# branch.net
KiCad netlist of a schematic drawn in EAGLE
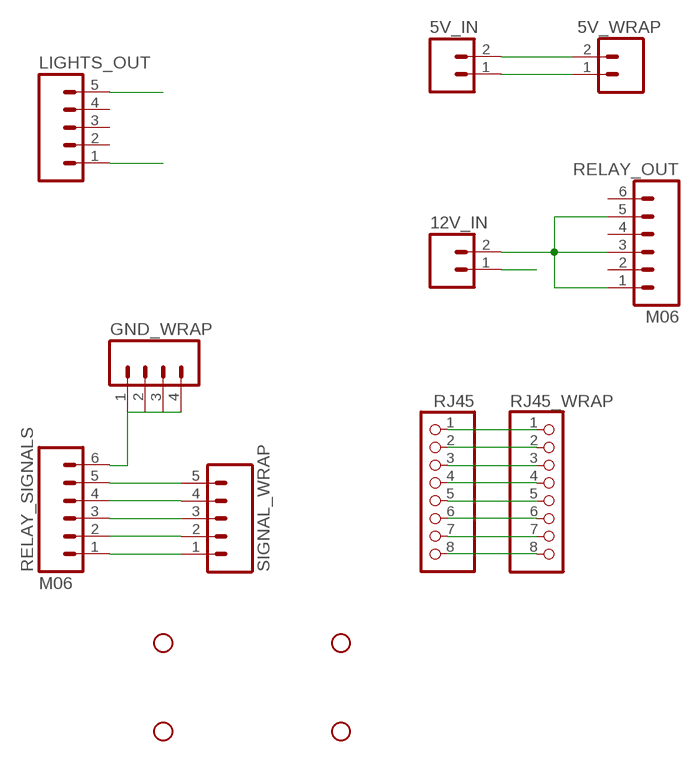
[diagram p0: schematic, sheet 1]

(export (version "E")
  (design (tool "Eeschema 10.0.6"))
  (components
    (comp (ref "5V_IN")
      (value "M021X02-MTA")
      (footprint "eagle-import:1X02-MTA")
      (fields (field (name "PARTNUMBER") "A1921-ND"))
      (libsource (lib "eagle-import") (part "M021X02-MTA"))
    )
    (comp (ref "5V_WRAP")
      (value "M02PTH")
      (footprint "eagle-import:1X02")
      (libsource (lib "eagle-import") (part "M02PTH"))
    )
    (comp (ref "12V_IN")
      (value "M021X02-MTA")
      (footprint "eagle-import:1X02-MTA")
      (fields (field (name "PARTNUMBER") "A1921-ND"))
      (libsource (lib "eagle-import") (part "M021X02-MTA"))
    )
    (comp (ref "GND_WRAP")
      (value "M04PTH")
      (footprint "eagle-import:1X04")
      (libsource (lib "eagle-import") (part "M04PTH"))
    )
    (comp (ref "LIGHTS_OUT")
      (value "M05MTA")
      (footprint "eagle-import:1X05-MTA")
      (fields (field (name "PARTNUMBER") "A19471-ND"))
      (libsource (lib "eagle-import") (part "M05MTA"))
    )
    (comp (ref "RELAY_OUT")
      (value "M06")
      (footprint "eagle-import:1X06-MTA")
      (fields (field (name "PARTNUMBER") "A1923-ND"))
      (libsource (lib "eagle-import") (part "M06"))
    )
    (comp (ref "RELAY_SIGNALS")
      (value "M06")
      (footprint "eagle-import:1X06-MTA")
      (fields (field (name "PARTNUMBER") "A1923-ND"))
      (libsource (lib "eagle-import") (part "M06"))
    )
    (comp (ref "RJ45")
      (value "PINHD-1X8")
      (footprint "eagle-import:1X08")
      (fields (field (name "PARTNUMBER") "965"))
      (libsource (lib "eagle-import") (part "PINHD-1X8"))
    )
    (comp (ref "RJ45_WRAP")
      (value "PINHD-1X8")
      (footprint "eagle-import:1X08")
      (fields (field (name "PARTNUMBER") "965"))
      (libsource (lib "eagle-import") (part "PINHD-1X8"))
    )
    (comp (ref "SIGNAL_WRAP")
      (value "M05PTH")
      (footprint "eagle-import:1X05")
      (fields (field (name "PARTNUMBER") "965"))
      (libsource (lib "eagle-import") (part "M05PTH"))
    )
    (comp (ref "STANDOFF1")
      (value "STAND-OFF")
      (footprint "eagle-import:STAND-OFF")
      (libsource (lib "eagle-import") (part "STAND-OFF"))
    )
    (comp (ref "STANDOFF2")
      (value "STAND-OFF")
      (footprint "eagle-import:STAND-OFF")
      (libsource (lib "eagle-import") (part "STAND-OFF"))
    )
    (comp (ref "STANDOFF3")
      (value "STAND-OFF")
      (footprint "eagle-import:STAND-OFF")
      (libsource (lib "eagle-import") (part "STAND-OFF"))
    )
    (comp (ref "STANDOFF4")
      (value "STAND-OFF")
      (footprint "eagle-import:STAND-OFF")
      (libsource (lib "eagle-import") (part "STAND-OFF"))
    )
  )
  (nets
    (net (code "1") (name "/GND") (class "Default")
      (node (ref "12V_IN") (pin "1") (pinfunction "1_1") (pintype "passive"))
      (node (ref "5V_IN") (pin "1") (pinfunction "1_1") (pintype "passive"))
      (node (ref "5V_WRAP") (pin "1") (pinfunction "1_1") (pintype "passive"))
      (node (ref "GND_WRAP") (pin "1") (pinfunction "1_1") (pintype "passive"))
      (node (ref "GND_WRAP") (pin "2") (pinfunction "2_2") (pintype "passive"))
      (node (ref "GND_WRAP") (pin "3") (pinfunction "3_3") (pintype "passive"))
      (node (ref "GND_WRAP") (pin "4") (pinfunction "4_4") (pintype "passive"))
      (node (ref "LIGHTS_OUT") (pin "1") (pinfunction "1_1") (pintype "passive"))
      (node (ref "RELAY_SIGNALS") (pin "6") (pinfunction "6_6") (pintype "passive"))
    )
    (net (code "2") (name "Net-(5V_IN-Pad2)") (class "Default")
      (node (ref "5V_IN") (pin "2") (pinfunction "2_2") (pintype "passive"))
      (node (ref "5V_WRAP") (pin "2") (pinfunction "2_2") (pintype "passive"))
    )
    (net (code "3") (name "Net-(12V_IN-Pad2)") (class "Default")
      (node (ref "12V_IN") (pin "2") (pinfunction "2_2") (pintype "passive"))
      (node (ref "RELAY_OUT") (pin "1") (pinfunction "1_1") (pintype "passive"))
      (node (ref "RELAY_OUT") (pin "3") (pinfunction "3_3") (pintype "passive"))
      (node (ref "RELAY_OUT") (pin "5") (pinfunction "5_5") (pintype "passive"))
    )
    (net (code "4") (name "Net-(RELAY_SIGNALS-Pad1)") (class "Default")
      (node (ref "RELAY_SIGNALS") (pin "1") (pinfunction "1_1") (pintype "passive"))
      (node (ref "SIGNAL_WRAP") (pin "1") (pinfunction "1_1") (pintype "passive"))
    )
    (net (code "5") (name "Net-(RELAY_SIGNALS-Pad2)") (class "Default")
      (node (ref "RELAY_SIGNALS") (pin "2") (pinfunction "2_2") (pintype "passive"))
      (node (ref "SIGNAL_WRAP") (pin "2") (pinfunction "2_2") (pintype "passive"))
    )
    (net (code "6") (name "Net-(RELAY_SIGNALS-Pad3)") (class "Default")
      (node (ref "RELAY_SIGNALS") (pin "3") (pinfunction "3_3") (pintype "passive"))
      (node (ref "SIGNAL_WRAP") (pin "3") (pinfunction "3_3") (pintype "passive"))
    )
    (net (code "7") (name "Net-(RELAY_SIGNALS-Pad4)") (class "Default")
      (node (ref "RELAY_SIGNALS") (pin "4") (pinfunction "4_4") (pintype "passive"))
      (node (ref "SIGNAL_WRAP") (pin "4") (pinfunction "4_4") (pintype "passive"))
    )
    (net (code "8") (name "Net-(RELAY_SIGNALS-Pad5)") (class "Default")
      (node (ref "RELAY_SIGNALS") (pin "5") (pinfunction "5_5") (pintype "passive"))
      (node (ref "SIGNAL_WRAP") (pin "5") (pinfunction "5_5") (pintype "passive"))
    )
    (net (code "9") (name "Net-(RJ45-Pad1)") (class "Default")
      (node (ref "RJ45") (pin "1") (pinfunction "1_1") (pintype "passive"))
      (node (ref "RJ45_WRAP") (pin "1") (pinfunction "1_1") (pintype "passive"))
    )
    (net (code "10") (name "Net-(RJ45-Pad2)") (class "Default")
      (node (ref "RJ45") (pin "2") (pinfunction "2_2") (pintype "passive"))
      (node (ref "RJ45_WRAP") (pin "2") (pinfunction "2_2") (pintype "passive"))
    )
    (net (code "11") (name "Net-(RJ45-Pad3)") (class "Default")
      (node (ref "RJ45") (pin "3") (pinfunction "3_3") (pintype "passive"))
      (node (ref "RJ45_WRAP") (pin "3") (pinfunction "3_3") (pintype "passive"))
    )
    (net (code "12") (name "Net-(RJ45-Pad4)") (class "Default")
      (node (ref "RJ45") (pin "4") (pinfunction "4_4") (pintype "passive"))
      (node (ref "RJ45_WRAP") (pin "4") (pinfunction "4_4") (pintype "passive"))
    )
    (net (code "13") (name "Net-(RJ45-Pad5)") (class "Default")
      (node (ref "RJ45") (pin "5") (pinfunction "5_5") (pintype "passive"))
      (node (ref "RJ45_WRAP") (pin "5") (pinfunction "5_5") (pintype "passive"))
    )
    (net (code "14") (name "Net-(RJ45-Pad6)") (class "Default")
      (node (ref "RJ45") (pin "6") (pinfunction "6_6") (pintype "passive"))
      (node (ref "RJ45_WRAP") (pin "6") (pinfunction "6_6") (pintype "passive"))
    )
    (net (code "15") (name "Net-(RJ45-Pad7)") (class "Default")
      (node (ref "RJ45") (pin "7") (pinfunction "7_7") (pintype "passive"))
      (node (ref "RJ45_WRAP") (pin "7") (pinfunction "7_7") (pintype "passive"))
    )
    (net (code "16") (name "Net-(RJ45-Pad8)") (class "Default")
      (node (ref "RJ45") (pin "8") (pinfunction "8_8") (pintype "passive"))
      (node (ref "RJ45_WRAP") (pin "8") (pinfunction "8_8") (pintype "passive"))
    )
    (net (code "17") (name "unconnected-(LIGHTS_OUT-Pad2)") (class "Default")
      (node (ref "LIGHTS_OUT") (pin "2") (pinfunction "2_2") (pintype "passive"))
    )
    (net (code "18") (name "unconnected-(LIGHTS_OUT-Pad3)") (class "Default")
      (node (ref "LIGHTS_OUT") (pin "3") (pinfunction "3_3") (pintype "passive"))
    )
    (net (code "19") (name "unconnected-(LIGHTS_OUT-Pad4)") (class "Default")
      (node (ref "LIGHTS_OUT") (pin "4") (pinfunction "4_4") (pintype "passive"))
    )
    (net (code "20") (name "unconnected-(LIGHTS_OUT-Pad5)") (class "Default")
      (node (ref "LIGHTS_OUT") (pin "5") (pinfunction "5_5") (pintype "passive"))
    )
    (net (code "21") (name "unconnected-(RELAY_OUT-Pad2)") (class "Default")
      (node (ref "RELAY_OUT") (pin "2") (pinfunction "2_2") (pintype "passive"))
    )
    (net (code "22") (name "unconnected-(RELAY_OUT-Pad4)") (class "Default")
      (node (ref "RELAY_OUT") (pin "4") (pinfunction "4_4") (pintype "passive"))
    )
    (net (code "23") (name "unconnected-(RELAY_OUT-Pad6)") (class "Default")
      (node (ref "RELAY_OUT") (pin "6") (pinfunction "6_6") (pintype "passive"))
    )
  )
)
